# PowerSupply.net
KiCad netlist of a schematic drawn in Altium Designer
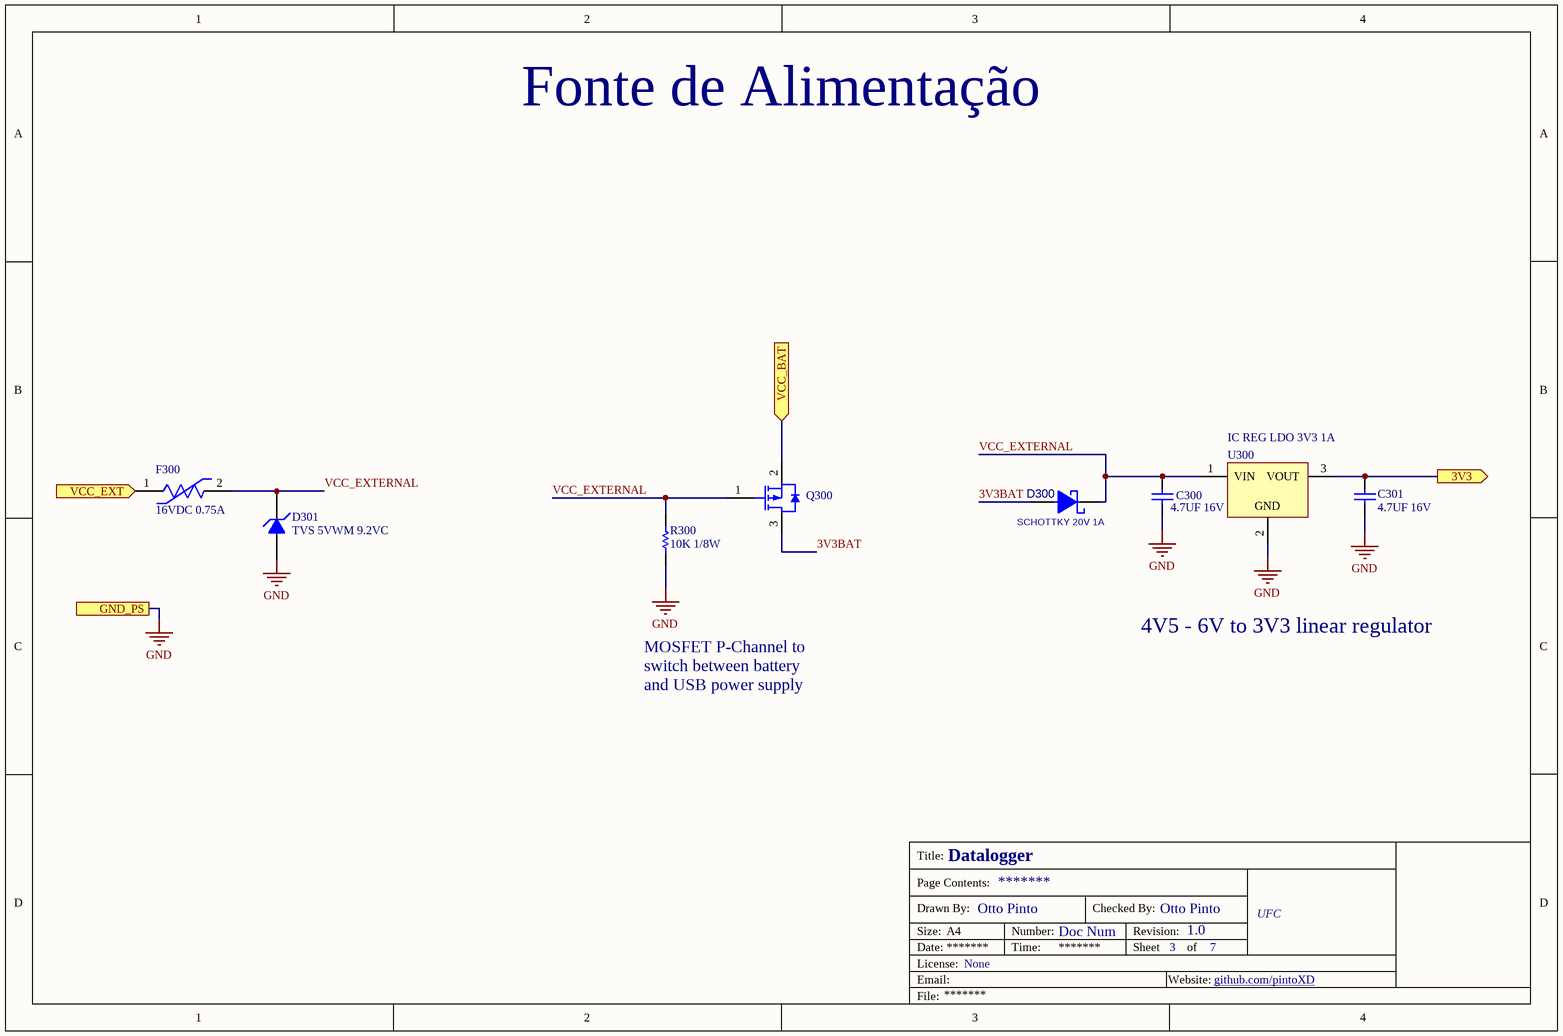
[diagram p0: PowerSupply.SchDoc]

(export (version "E")
  (design (tool "Eeschema 10.0.6"))
  (components
    (comp (ref "C300")
      (value "4.7UF 16V")
      (footprint "CC2012-0805")
      (description "CAP CER 4.7UF 16V X7R 0805")
      (fields (field (name "TOLERANCE") "10%") (field (name "SOURCE") "mits.SchLib"))
      (libsource (lib "Mobit Brasil Ltda") (part "Symbol"))
    )
    (comp (ref "C301")
      (value "4.7UF 16V")
      (footprint "CC2012-0805")
      (description "CAP CER 4.7UF 16V X7R 0805")
      (fields (field (name "TOLERANCE") "10%") (field (name "SOURCE") "mits.SchLib"))
      (libsource (lib "Mobit Brasil Ltda") (part "Symbol"))
    )
    (comp (ref "D300")
      (value "SCHOTTKY 20V 1A")
      (footprint "SOD-323")
      (description "DIODE SCHOTTKY 20V 1A SOD323")
      (fields
        (field (name "MANUFACTURER") "ON Semiconductor")
        (field (name "MANUFACTURER PART NUMBER") "NSR0320MW2T1G")
        (field (name "SOURCE") "mits.SchLib")
      )
      (libsource (lib "") (part "Symbol_1"))
    )
    (comp (ref "D301")
      (value "TVS 5VWM 9.2VC")
      (footprint "DO-214AA(SMB)")
      (description "TVS DIODE 5VWM 9.2VC SMB")
      (fields (field (name "VOLTAGE") "5V"))
      (libsource (lib "Mobit Brasil Ltda") (part "TVS DIODE"))
    )
    (comp (ref "F300")
      (value "16VDC 0.75A")
      (footprint "FP-0ZCJ0035FF2G-MFG")
      (libsource (lib "Mobit Brasil Ltda") (part "fdf083d5f6389a9a1c4e51137f46658"))
    )
    (comp (ref "Q300")
      (value "IC MOSFET P_CHANNEL 20V 6A")
      (footprint "SOT-23")
      (description "Small Low ON Resistance MOSFET P-Channel 20V 6A 3-Pin SOT-23F T/R")
      (fields
        (field (name "MANUFACTURER") "Toshiba")
        (field (name "MANUFACTURER PART NUMBER") "SSM3J358R,LF")
      )
      (libsource (lib "lib_datalogger") (part "IC MOSFET P_CHANNEL 20V 6A"))
    )
    (comp (ref "R300")
      (value "10K 1/8W")
      (footprint "CR2012-0805")
      (description "RES 0805 10K Ohm 0.1% 1/10W  SMD")
      (fields
        (field (name "MANUFACTURER PART NUMBER") "ERJ-6ENF1002V")
        (field (name "MANUFACTURER") "Panasonic Electronic Components")
        (field (name "SOURCE") "mits.SchLib")
      )
      (libsource (lib "") (part "Symbol_2"))
    )
    (comp (ref "U300")
      (value "IC REG LDO 3V3 1A")
      (footprint "SOT-223")
      (description "IC REG LDO 3.3V 1A SOT223")
      (fields
        (field (name "MANUFACTURER") "Diodes")
        (field (name "MANUFACTURER PART NUMBER") "AP2114HA-3.3TRG1")
      )
      (libsource (lib "lib_datalogger") (part "IC REG LDO 3V3 1A"))
    )
  )
  (nets
    (net (code "1") (name "/3V3") (class "Default")
      (node (ref "C301") (pin "2") (pinfunction "2_2") (pintype "passive"))
      (node (ref "U300") (pin "3") (pinfunction "VOUT_3") (pintype "power_in"))
    )
    (net (code "2") (name "/3V3BAT") (class "Default")
      (node (ref "D300") (pin "A") (pinfunction "A_A") (pintype "passive"))
      (node (ref "Q300") (pin "3") (pinfunction "DRAIN_3") (pintype "passive"))
    )
    (net (code "3") (name "/VCC_BAT") (class "Default")
      (node (ref "Q300") (pin "2") (pinfunction "SOURCE_2") (pintype "passive"))
    )
    (net (code "4") (name "/VCC_EXT") (class "Default")
      (node (ref "F300") (pin "1") (pinfunction "1_1") (pintype "passive"))
    )
    (net (code "5") (name "/VCC_EXTERNAL") (class "Default")
      (node (ref "C300") (pin "2") (pinfunction "2_2") (pintype "passive"))
      (node (ref "D300") (pin "K") (pinfunction "K_K") (pintype "passive"))
      (node (ref "D301") (pin "1") (pinfunction "K_1") (pintype "passive"))
      (node (ref "F300") (pin "2") (pinfunction "2_2") (pintype "passive"))
      (node (ref "Q300") (pin "1") (pinfunction "GATE_1") (pintype "passive"))
      (node (ref "R300") (pin "2") (pinfunction "2_2") (pintype "passive"))
      (node (ref "U300") (pin "1") (pinfunction "VIN_1") (pintype "power_in"))
    )
    (net (code "6") (name "GND") (class "Default")
      (node (ref "C300") (pin "1") (pinfunction "1_1") (pintype "passive"))
      (node (ref "C301") (pin "1") (pinfunction "1_1") (pintype "passive"))
      (node (ref "D301") (pin "2") (pinfunction "A_2") (pintype "passive"))
      (node (ref "R300") (pin "1") (pinfunction "1_1") (pintype "passive"))
      (node (ref "U300") (pin "2") (pinfunction "GND_2") (pintype "power_in"))
    )
  )
)
